# ESP012-16-Channel-PWM1.net
KiCad netlist of a schematic drawn in EAGLE
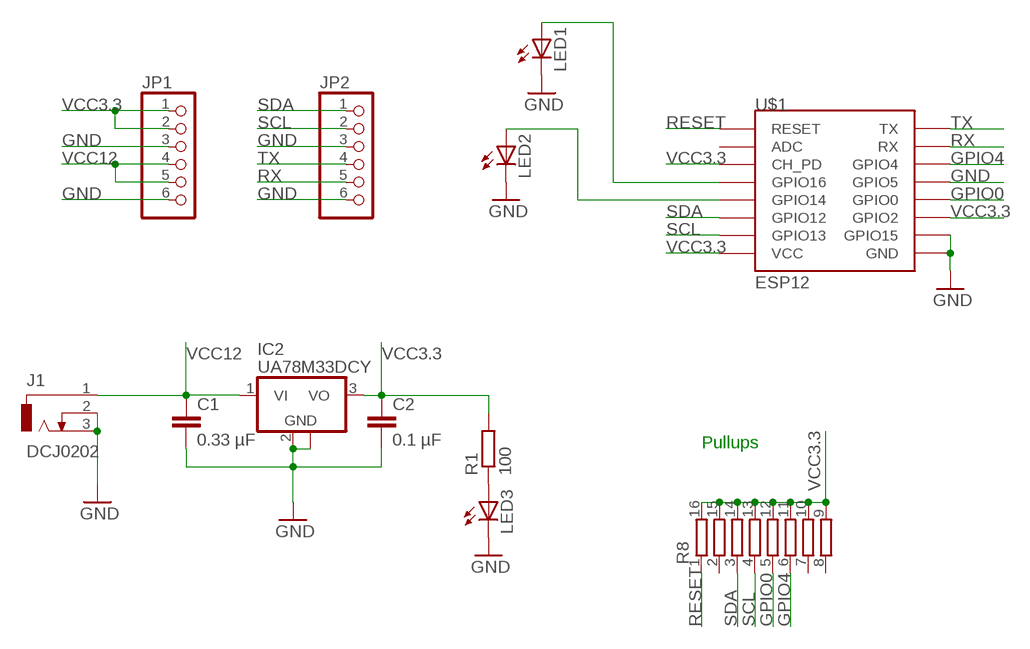
[diagram p0: schematic, sheet 1, part 1 of 2]
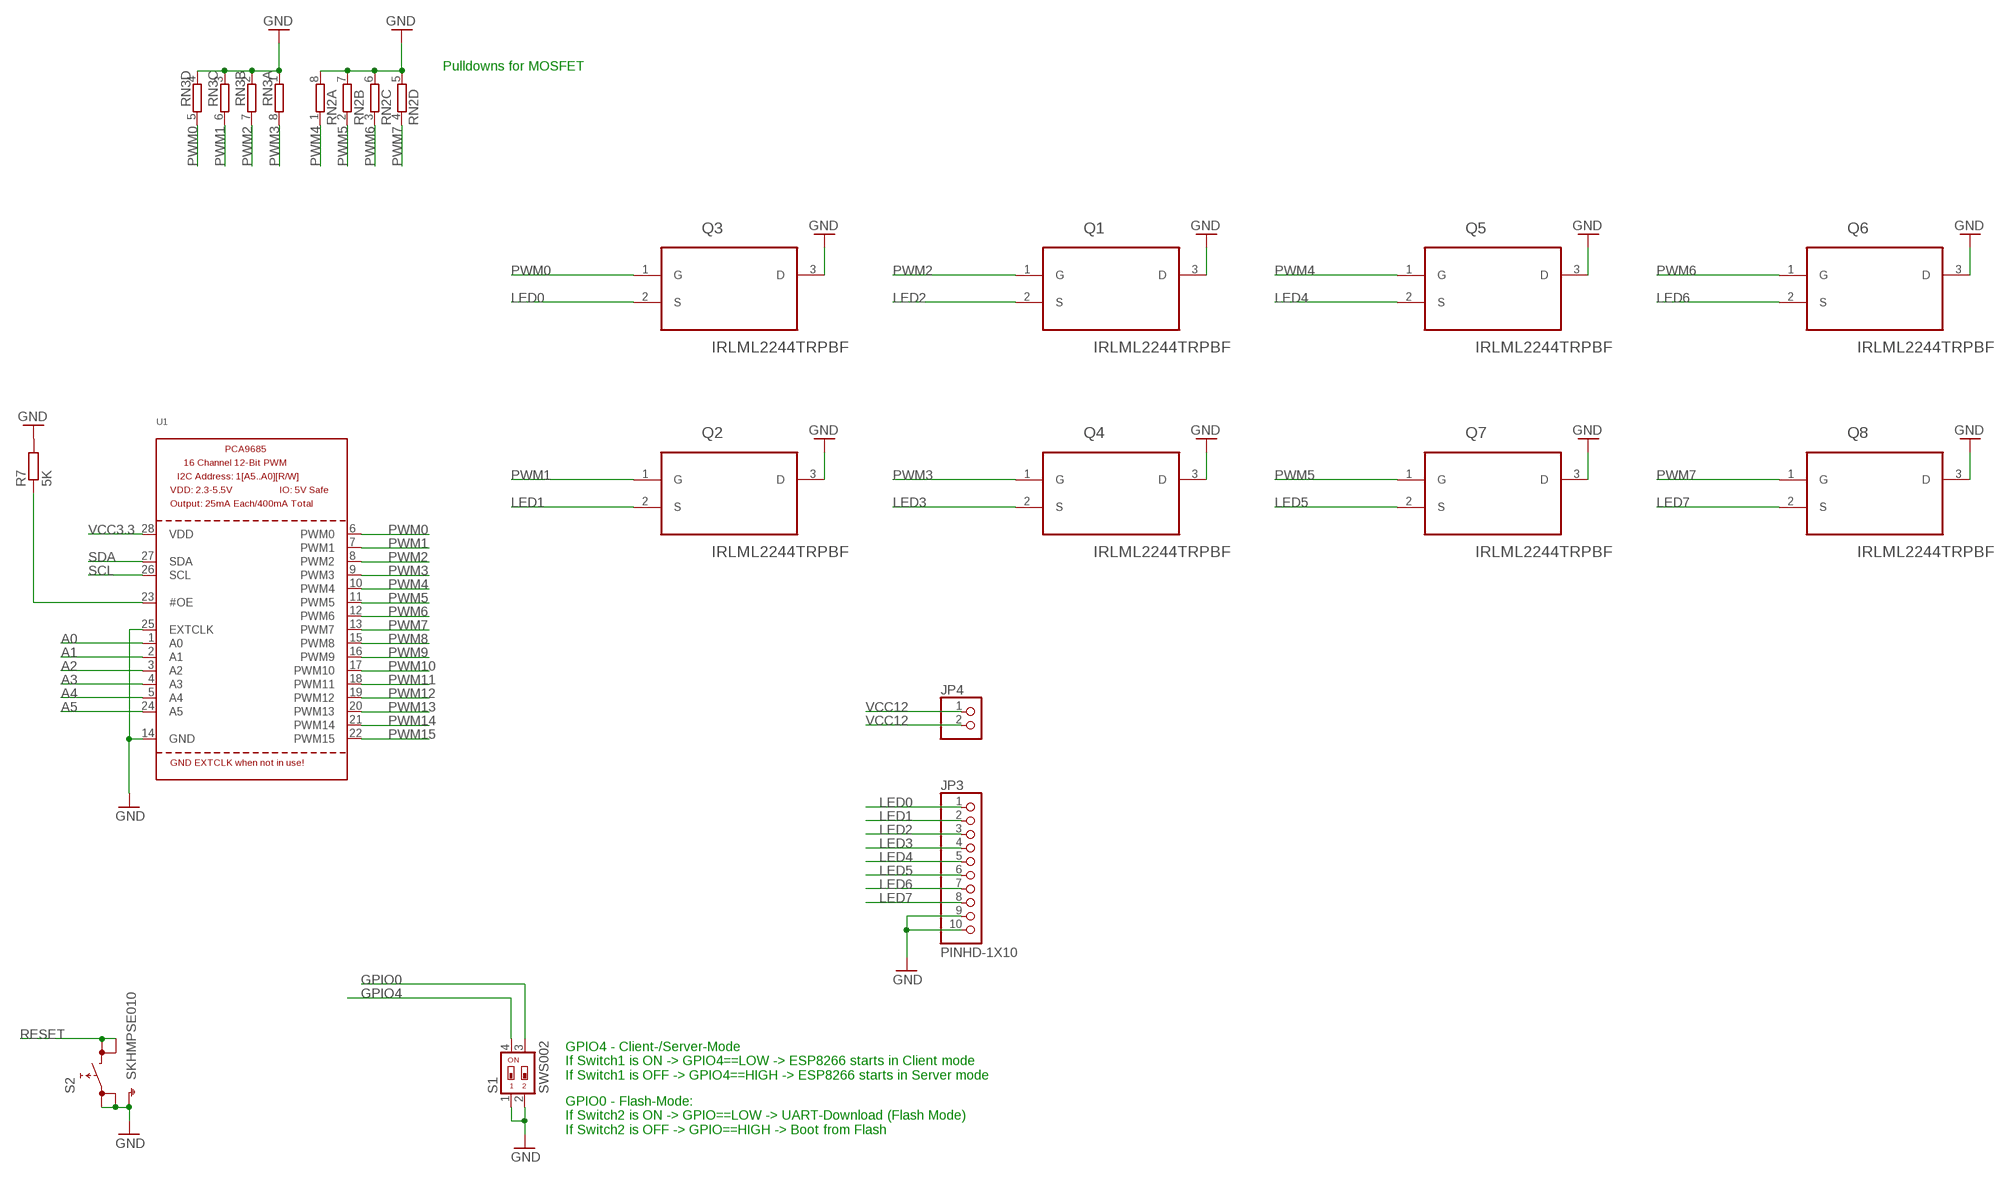
[diagram p1: schematic, sheet 1, part 2 of 2]

(export (version "E")
  (design (tool "Eeschema 10.0.6"))
  (components
    (comp (ref "C1")
      (value "0.33 µF")
      (footprint "eagle-import:C025-024X044")
      (libsource (lib "eagle-import") (part "C-EU025-024X044"))
    )
    (comp (ref "C2")
      (value "0.1 µF")
      (footprint "eagle-import:C025-024X044")
      (libsource (lib "eagle-import") (part "C-EU025-024X044"))
    )
    (comp (ref "IC2")
      (value "UA78M33DCY")
      (footprint "eagle-import:SOT223")
      (libsource (lib "eagle-import") (part "UA78MDCY33"))
    )
    (comp (ref "J1")
      (value "DCJ0202")
      (footprint "eagle-import:DCJ0202")
      (libsource (lib "eagle-import") (part "DCJ0202"))
    )
    (comp (ref "JP1")
      (value "PINHD-1X6")
      (footprint "eagle-import:1X06")
      (libsource (lib "eagle-import") (part "PINHD-1X6"))
    )
    (comp (ref "JP2")
      (value "PINHD-1X6")
      (footprint "eagle-import:1X06")
      (libsource (lib "eagle-import") (part "PINHD-1X6"))
    )
    (comp (ref "JP3")
      (value "PINHD-1X10")
      (footprint "eagle-import:1X10-BIG")
      (libsource (lib "eagle-import") (part "PINHD-1X10"))
    )
    (comp (ref "JP4")
      (value "PINHD-1X2")
      (footprint "eagle-import:1X02")
      (libsource (lib "eagle-import") (part "PINHD-1X2"))
    )
    (comp (ref "LED1")
      (value "LEDCHIP-LED0805")
      (footprint "eagle-import:CHIP-LED0805")
      (libsource (lib "eagle-import") (part "LEDCHIP-LED0805"))
    )
    (comp (ref "LED2")
      (value "LEDCHIP-LED0805")
      (footprint "eagle-import:CHIP-LED0805")
      (libsource (lib "eagle-import") (part "LEDCHIP-LED0805"))
    )
    (comp (ref "LED3")
      (value "LEDCHIP-LED0805")
      (footprint "eagle-import:CHIP-LED0805")
      (libsource (lib "eagle-import") (part "LEDCHIP-LED0805"))
    )
    (comp (ref "Q1")
      (value "IRLML2244TRPBF")
      (footprint "eagle-import:SOT95P237X112-3N")
      (libsource (lib "eagle-import") (part "IRLML2244TRPBF"))
    )
    (comp (ref "Q2")
      (value "IRLML2244TRPBF")
      (footprint "eagle-import:SOT95P237X112-3N")
      (libsource (lib "eagle-import") (part "IRLML2244TRPBF"))
    )
    (comp (ref "Q3")
      (value "IRLML2244TRPBF")
      (footprint "eagle-import:SOT95P237X112-3N")
      (libsource (lib "eagle-import") (part "IRLML2244TRPBF"))
    )
    (comp (ref "Q4")
      (value "IRLML2244TRPBF")
      (footprint "eagle-import:SOT95P237X112-3N")
      (libsource (lib "eagle-import") (part "IRLML2244TRPBF"))
    )
    (comp (ref "Q5")
      (value "IRLML2244TRPBF")
      (footprint "eagle-import:SOT95P237X112-3N")
      (libsource (lib "eagle-import") (part "IRLML2244TRPBF"))
    )
    (comp (ref "Q6")
      (value "IRLML2244TRPBF")
      (footprint "eagle-import:SOT95P237X112-3N")
      (libsource (lib "eagle-import") (part "IRLML2244TRPBF"))
    )
    (comp (ref "Q7")
      (value "IRLML2244TRPBF")
      (footprint "eagle-import:SOT95P237X112-3N")
      (libsource (lib "eagle-import") (part "IRLML2244TRPBF"))
    )
    (comp (ref "Q8")
      (value "IRLML2244TRPBF")
      (footprint "eagle-import:SOT95P237X112-3N")
      (libsource (lib "eagle-import") (part "IRLML2244TRPBF"))
    )
    (comp (ref "R1")
      (value "100")
      (footprint "eagle-import:MINI_MELF-0207R")
      (libsource (lib "eagle-import") (part "R-EU_MELF0207R"))
    )
    (comp (ref "R7")
      (value "5K")
      (footprint "eagle-import:MINI_MELF-0207R")
      (libsource (lib "eagle-import") (part "R-EU_MELF0207R"))
    )
    (comp (ref "R8")
      (value "2QSP16-8")
      (footprint "eagle-import:2QSP16")
      (libsource (lib "eagle-import") (part "2QSP16-8"))
    )
    (comp (ref "RN2")
      (value "4R-NEXBS8V")
      (footprint "eagle-import:EXBS8V")
      (libsource (lib "eagle-import") (part "4R-NEXBS8V"))
    )
    (comp (ref "RN3")
      (value "4R-NEXBS8V")
      (footprint "eagle-import:EXBS8V")
      (libsource (lib "eagle-import") (part "4R-NEXBS8V"))
    )
    (comp (ref "S1")
      (value "SWS002")
      (footprint "eagle-import:SMS-002")
      (libsource (lib "eagle-import") (part "SWS002"))
    )
    (comp (ref "S2")
      (value "SKHMPSE010")
      (footprint "eagle-import:SKHMPXE010")
      (libsource (lib "eagle-import") (part "SKHMPE010S"))
    )
    (comp (ref "U$1")
      (value "ESP12")
      (footprint "eagle-import:ESP12")
      (libsource (lib "eagle-import") (part "ESP12"))
    )
    (comp (ref "U1")
      (value "PCA9685")
      (footprint "eagle-import:TSSOP28")
      (libsource (lib "eagle-import") (part "PCA9685"))
    )
  )
  (nets
    (net (code "1") (name "/A0") (class "Default")
      (node (ref "U1") (pin "1") (pinfunction "A0_1") (pintype "bidirectional"))
    )
    (net (code "2") (name "/A1") (class "Default")
      (node (ref "U1") (pin "2") (pinfunction "A1_2") (pintype "bidirectional"))
    )
    (net (code "3") (name "/A2") (class "Default")
      (node (ref "U1") (pin "3") (pinfunction "A2_3") (pintype "bidirectional"))
    )
    (net (code "4") (name "/A3") (class "Default")
      (node (ref "U1") (pin "4") (pinfunction "A3_4") (pintype "bidirectional"))
    )
    (net (code "5") (name "/A4") (class "Default")
      (node (ref "U1") (pin "5") (pinfunction "A4_5") (pintype "bidirectional"))
    )
    (net (code "6") (name "/A5") (class "Default")
      (node (ref "U1") (pin "24") (pinfunction "A5_24") (pintype "bidirectional"))
    )
    (net (code "7") (name "/GPIO0") (class "Default")
      (node (ref "R8") (pin "5") (pinfunction "5_5") (pintype "passive"))
      (node (ref "S1") (pin "3") (pinfunction "3_3") (pintype "passive"))
      (node (ref "U$1") (pin "GPIO0") (pinfunction "GPIO0_GPIO0") (pintype "bidirectional"))
    )
    (net (code "8") (name "/GPIO4") (class "Default")
      (node (ref "R8") (pin "6") (pinfunction "6_6") (pintype "passive"))
      (node (ref "S1") (pin "4") (pinfunction "4_4") (pintype "passive"))
      (node (ref "U$1") (pin "GPIO4") (pinfunction "GPIO4_GPIO4") (pintype "bidirectional"))
    )
    (net (code "9") (name "/LED0") (class "Default")
      (node (ref "JP3") (pin "1") (pinfunction "1_1") (pintype "passive"))
      (node (ref "Q3") (pin "2") (pinfunction "S_2") (pintype "passive"))
    )
    (net (code "10") (name "/LED1") (class "Default")
      (node (ref "JP3") (pin "2") (pinfunction "2_2") (pintype "passive"))
      (node (ref "Q2") (pin "2") (pinfunction "S_2") (pintype "passive"))
    )
    (net (code "11") (name "/LED2") (class "Default")
      (node (ref "JP3") (pin "3") (pinfunction "3_3") (pintype "passive"))
      (node (ref "Q1") (pin "2") (pinfunction "S_2") (pintype "passive"))
    )
    (net (code "12") (name "/LED3") (class "Default")
      (node (ref "JP3") (pin "4") (pinfunction "4_4") (pintype "passive"))
      (node (ref "Q4") (pin "2") (pinfunction "S_2") (pintype "passive"))
    )
    (net (code "13") (name "/LED4") (class "Default")
      (node (ref "JP3") (pin "5") (pinfunction "5_5") (pintype "passive"))
      (node (ref "Q5") (pin "2") (pinfunction "S_2") (pintype "passive"))
    )
    (net (code "14") (name "/LED5") (class "Default")
      (node (ref "JP3") (pin "6") (pinfunction "6_6") (pintype "passive"))
      (node (ref "Q7") (pin "2") (pinfunction "S_2") (pintype "passive"))
    )
    (net (code "15") (name "/LED6") (class "Default")
      (node (ref "JP3") (pin "7") (pinfunction "7_7") (pintype "passive"))
      (node (ref "Q6") (pin "2") (pinfunction "S_2") (pintype "passive"))
    )
    (net (code "16") (name "/LED7") (class "Default")
      (node (ref "JP3") (pin "8") (pinfunction "8_8") (pintype "passive"))
      (node (ref "Q8") (pin "2") (pinfunction "S_2") (pintype "passive"))
    )
    (net (code "17") (name "/PWM0") (class "Default")
      (node (ref "Q3") (pin "1") (pinfunction "G_1") (pintype "passive"))
      (node (ref "RN3") (pin "5") (pinfunction "2_5") (pintype "passive"))
      (node (ref "U1") (pin "6") (pinfunction "PWM0_6") (pintype "output"))
    )
    (net (code "18") (name "/PWM1") (class "Default")
      (node (ref "Q2") (pin "1") (pinfunction "G_1") (pintype "passive"))
      (node (ref "RN3") (pin "6") (pinfunction "2_6") (pintype "passive"))
      (node (ref "U1") (pin "7") (pinfunction "PWM1_7") (pintype "output"))
    )
    (net (code "19") (name "/PWM2") (class "Default")
      (node (ref "Q1") (pin "1") (pinfunction "G_1") (pintype "passive"))
      (node (ref "RN3") (pin "7") (pinfunction "2_7") (pintype "passive"))
      (node (ref "U1") (pin "8") (pinfunction "PWM2_8") (pintype "output"))
    )
    (net (code "20") (name "/PWM3") (class "Default")
      (node (ref "Q4") (pin "1") (pinfunction "G_1") (pintype "passive"))
      (node (ref "RN3") (pin "8") (pinfunction "2_8") (pintype "passive"))
      (node (ref "U1") (pin "9") (pinfunction "PWM3_9") (pintype "output"))
    )
    (net (code "21") (name "/PWM4") (class "Default")
      (node (ref "Q5") (pin "1") (pinfunction "G_1") (pintype "passive"))
      (node (ref "RN2") (pin "1") (pinfunction "1_1") (pintype "passive"))
      (node (ref "U1") (pin "10") (pinfunction "PWM4_10") (pintype "output"))
    )
    (net (code "22") (name "/PWM5") (class "Default")
      (node (ref "Q7") (pin "1") (pinfunction "G_1") (pintype "passive"))
      (node (ref "RN2") (pin "2") (pinfunction "1_2") (pintype "passive"))
      (node (ref "U1") (pin "11") (pinfunction "PWM5_11") (pintype "output"))
    )
    (net (code "23") (name "/PWM6") (class "Default")
      (node (ref "Q6") (pin "1") (pinfunction "G_1") (pintype "passive"))
      (node (ref "RN2") (pin "3") (pinfunction "1_3") (pintype "passive"))
      (node (ref "U1") (pin "12") (pinfunction "PWM6_12") (pintype "output"))
    )
    (net (code "24") (name "/PWM7") (class "Default")
      (node (ref "Q8") (pin "1") (pinfunction "G_1") (pintype "passive"))
      (node (ref "RN2") (pin "4") (pinfunction "1_4") (pintype "passive"))
      (node (ref "U1") (pin "13") (pinfunction "PWM7_13") (pintype "output"))
    )
    (net (code "25") (name "/PWM8") (class "Default")
      (node (ref "U1") (pin "15") (pinfunction "PWM8_15") (pintype "output"))
    )
    (net (code "26") (name "/PWM9") (class "Default")
      (node (ref "U1") (pin "16") (pinfunction "PWM9_16") (pintype "output"))
    )
    (net (code "27") (name "/PWM10") (class "Default")
      (node (ref "U1") (pin "17") (pinfunction "PWM10_17") (pintype "output"))
    )
    (net (code "28") (name "/PWM11") (class "Default")
      (node (ref "U1") (pin "18") (pinfunction "PWM11_18") (pintype "output"))
    )
    (net (code "29") (name "/PWM12") (class "Default")
      (node (ref "U1") (pin "19") (pinfunction "PWM12_19") (pintype "output"))
    )
    (net (code "30") (name "/PWM13") (class "Default")
      (node (ref "U1") (pin "20") (pinfunction "PWM13_20") (pintype "output"))
    )
    (net (code "31") (name "/PWM14") (class "Default")
      (node (ref "U1") (pin "21") (pinfunction "PWM14_21") (pintype "output"))
    )
    (net (code "32") (name "/PWM15") (class "Default")
      (node (ref "U1") (pin "22") (pinfunction "PWM15_22") (pintype "output"))
    )
    (net (code "33") (name "/RESET") (class "Default")
      (node (ref "R8") (pin "1") (pinfunction "1_1") (pintype "passive"))
      (node (ref "S2") (pin "3") (pinfunction "2.1_3") (pintype "passive"))
      (node (ref "S2") (pin "4") (pinfunction "2.2_4") (pintype "passive"))
      (node (ref "U$1") (pin "RESET") (pinfunction "RESET_RESET") (pintype "bidirectional"))
    )
    (net (code "34") (name "/RX") (class "Default")
      (node (ref "JP2") (pin "5") (pinfunction "5_5") (pintype "passive"))
      (node (ref "U$1") (pin "RX") (pinfunction "RX_RX") (pintype "bidirectional"))
    )
    (net (code "35") (name "/SCL") (class "Default")
      (node (ref "JP2") (pin "2") (pinfunction "2_2") (pintype "passive"))
      (node (ref "R8") (pin "4") (pinfunction "4_4") (pintype "passive"))
      (node (ref "U$1") (pin "GPIO13") (pinfunction "GPIO13_GPIO13") (pintype "bidirectional"))
      (node (ref "U1") (pin "26") (pinfunction "SCL_26") (pintype "bidirectional"))
    )
    (net (code "36") (name "/SDA") (class "Default")
      (node (ref "JP2") (pin "1") (pinfunction "1_1") (pintype "passive"))
      (node (ref "R8") (pin "3") (pinfunction "3_3") (pintype "passive"))
      (node (ref "U$1") (pin "GPIO12") (pinfunction "GPIO12_GPIO12") (pintype "bidirectional"))
      (node (ref "U1") (pin "27") (pinfunction "SDA_27") (pintype "bidirectional"))
    )
    (net (code "37") (name "/TX") (class "Default")
      (node (ref "JP2") (pin "4") (pinfunction "4_4") (pintype "passive"))
      (node (ref "U$1") (pin "TX") (pinfunction "TX_TX") (pintype "bidirectional"))
    )
    (net (code "38") (name "/VCC3.3") (class "Default")
      (node (ref "C2") (pin "1") (pinfunction "1_1") (pintype "passive"))
      (node (ref "IC2") (pin "3") (pinfunction "VO_3") (pintype "passive"))
      (node (ref "JP1") (pin "1") (pinfunction "1_1") (pintype "passive"))
      (node (ref "JP1") (pin "2") (pinfunction "2_2") (pintype "passive"))
      (node (ref "R1") (pin "2") (pinfunction "2_2") (pintype "passive"))
      (node (ref "R8") (pin "10") (pinfunction "10_10") (pintype "passive"))
      (node (ref "R8") (pin "11") (pinfunction "11_11") (pintype "passive"))
      (node (ref "R8") (pin "12") (pinfunction "12_12") (pintype "passive"))
      (node (ref "R8") (pin "13") (pinfunction "13_13") (pintype "passive"))
      (node (ref "R8") (pin "14") (pinfunction "14_14") (pintype "passive"))
      (node (ref "R8") (pin "15") (pinfunction "15_15") (pintype "passive"))
      (node (ref "R8") (pin "16") (pinfunction "16_16") (pintype "passive"))
      (node (ref "R8") (pin "9") (pinfunction "9_9") (pintype "passive"))
      (node (ref "U$1") (pin "CH_PD") (pinfunction "CH_PD_CH_PD") (pintype "bidirectional"))
      (node (ref "U$1") (pin "GPIO2") (pinfunction "GPIO2_GPIO2") (pintype "bidirectional"))
      (node (ref "U$1") (pin "VCC") (pinfunction "VCC_VCC") (pintype "bidirectional"))
      (node (ref "U1") (pin "28") (pinfunction "VDD_28") (pintype "power_in"))
    )
    (net (code "39") (name "/VCC12") (class "Default")
      (node (ref "C1") (pin "1") (pinfunction "1_1") (pintype "passive"))
      (node (ref "IC2") (pin "1") (pinfunction "VI_1") (pintype "input"))
      (node (ref "J1") (pin "1") (pinfunction "1_1") (pintype "passive"))
      (node (ref "JP1") (pin "4") (pinfunction "4_4") (pintype "passive"))
      (node (ref "JP1") (pin "5") (pinfunction "5_5") (pintype "passive"))
      (node (ref "JP4") (pin "1") (pinfunction "1_1") (pintype "passive"))
      (node (ref "JP4") (pin "2") (pinfunction "2_2") (pintype "passive"))
    )
    (net (code "40") (name "GND") (class "Default")
      (node (ref "C1") (pin "2") (pinfunction "2_2") (pintype "passive"))
      (node (ref "C2") (pin "2") (pinfunction "2_2") (pintype "passive"))
      (node (ref "IC2") (pin "2") (pinfunction "GND_2") (pintype "passive"))
      (node (ref "IC2") (pin "4") (pinfunction "GND_4") (pintype "passive"))
      (node (ref "J1") (pin "2") (pinfunction "2_2") (pintype "passive"))
      (node (ref "J1") (pin "3") (pinfunction "3_3") (pintype "passive"))
      (node (ref "JP1") (pin "3") (pinfunction "3_3") (pintype "passive"))
      (node (ref "JP1") (pin "6") (pinfunction "6_6") (pintype "passive"))
      (node (ref "JP2") (pin "3") (pinfunction "3_3") (pintype "passive"))
      (node (ref "JP2") (pin "6") (pinfunction "6_6") (pintype "passive"))
      (node (ref "JP3") (pin "10") (pinfunction "10_10") (pintype "passive"))
      (node (ref "JP3") (pin "9") (pinfunction "9_9") (pintype "passive"))
      (node (ref "LED1") (pin "C") (pinfunction "C_C") (pintype "passive"))
      (node (ref "LED2") (pin "C") (pinfunction "C_C") (pintype "passive"))
      (node (ref "LED3") (pin "C") (pinfunction "C_C") (pintype "passive"))
      (node (ref "Q1") (pin "3") (pinfunction "D_3") (pintype "passive"))
      (node (ref "Q2") (pin "3") (pinfunction "D_3") (pintype "passive"))
      (node (ref "Q3") (pin "3") (pinfunction "D_3") (pintype "passive"))
      (node (ref "Q4") (pin "3") (pinfunction "D_3") (pintype "passive"))
      (node (ref "Q5") (pin "3") (pinfunction "D_3") (pintype "passive"))
      (node (ref "Q6") (pin "3") (pinfunction "D_3") (pintype "passive"))
      (node (ref "Q7") (pin "3") (pinfunction "D_3") (pintype "passive"))
      (node (ref "Q8") (pin "3") (pinfunction "D_3") (pintype "passive"))
      (node (ref "R7") (pin "2") (pinfunction "2_2") (pintype "passive"))
      (node (ref "RN2") (pin "5") (pinfunction "2_5") (pintype "passive"))
      (node (ref "RN2") (pin "6") (pinfunction "2_6") (pintype "passive"))
      (node (ref "RN2") (pin "7") (pinfunction "2_7") (pintype "passive"))
      (node (ref "RN2") (pin "8") (pinfunction "2_8") (pintype "passive"))
      (node (ref "RN3") (pin "1") (pinfunction "1_1") (pintype "passive"))
      (node (ref "RN3") (pin "2") (pinfunction "1_2") (pintype "passive"))
      (node (ref "RN3") (pin "3") (pinfunction "1_3") (pintype "passive"))
      (node (ref "RN3") (pin "4") (pinfunction "1_4") (pintype "passive"))
      (node (ref "S1") (pin "1") (pinfunction "1_1") (pintype "passive"))
      (node (ref "S1") (pin "2") (pinfunction "2_2") (pintype "passive"))
      (node (ref "S2") (pin "1") (pinfunction "1.1_1") (pintype "passive"))
      (node (ref "S2") (pin "2") (pinfunction "1.2_2") (pintype "passive"))
      (node (ref "S2") (pin "5") (pinfunction "SH_5") (pintype "passive"))
      (node (ref "U$1") (pin "GND") (pinfunction "GND_GND") (pintype "bidirectional"))
      (node (ref "U$1") (pin "GPIO15") (pinfunction "GPIO15_GPIO15") (pintype "bidirectional"))
      (node (ref "U$1") (pin "GPIO5") (pinfunction "GPIO5_GPIO5") (pintype "bidirectional"))
      (node (ref "U1") (pin "14") (pinfunction "GND_14") (pintype "power_in"))
      (node (ref "U1") (pin "25") (pinfunction "EXTCLK_25") (pintype "input"))
    )
    (net (code "41") (name "Net-(LED1-PadA)") (class "Default")
      (node (ref "LED1") (pin "A") (pinfunction "A_A") (pintype "passive"))
      (node (ref "U$1") (pin "GPIO16") (pinfunction "GPIO16_GPIO16") (pintype "bidirectional"))
    )
    (net (code "42") (name "Net-(LED2-PadA)") (class "Default")
      (node (ref "LED2") (pin "A") (pinfunction "A_A") (pintype "passive"))
      (node (ref "U$1") (pin "GPIO14") (pinfunction "GPIO14_GPIO14") (pintype "bidirectional"))
    )
    (net (code "43") (name "Net-(LED3-PadA)") (class "Default")
      (node (ref "LED3") (pin "A") (pinfunction "A_A") (pintype "passive"))
      (node (ref "R1") (pin "1") (pinfunction "1_1") (pintype "passive"))
    )
    (net (code "44") (name "Net-(U1-#OE)") (class "Default")
      (node (ref "R7") (pin "1") (pinfunction "1_1") (pintype "passive"))
      (node (ref "U1") (pin "23") (pinfunction "#OE_23") (pintype "input"))
    )
    (net (code "45") (name "unconnected-(R8-Pad2)") (class "Default")
      (node (ref "R8") (pin "2") (pinfunction "2_2") (pintype "passive"))
    )
    (net (code "46") (name "unconnected-(R8-Pad7)") (class "Default")
      (node (ref "R8") (pin "7") (pinfunction "7_7") (pintype "passive"))
    )
    (net (code "47") (name "unconnected-(R8-Pad8)") (class "Default")
      (node (ref "R8") (pin "8") (pinfunction "8_8") (pintype "passive"))
    )
    (net (code "48") (name "unconnected-(U$1-PadADC)") (class "Default")
      (node (ref "U$1") (pin "ADC") (pinfunction "ADC_ADC") (pintype "bidirectional"))
    )
  )
)
